# Stromversorgung-2.net
KiCad netlist of a schematic drawn in EAGLE
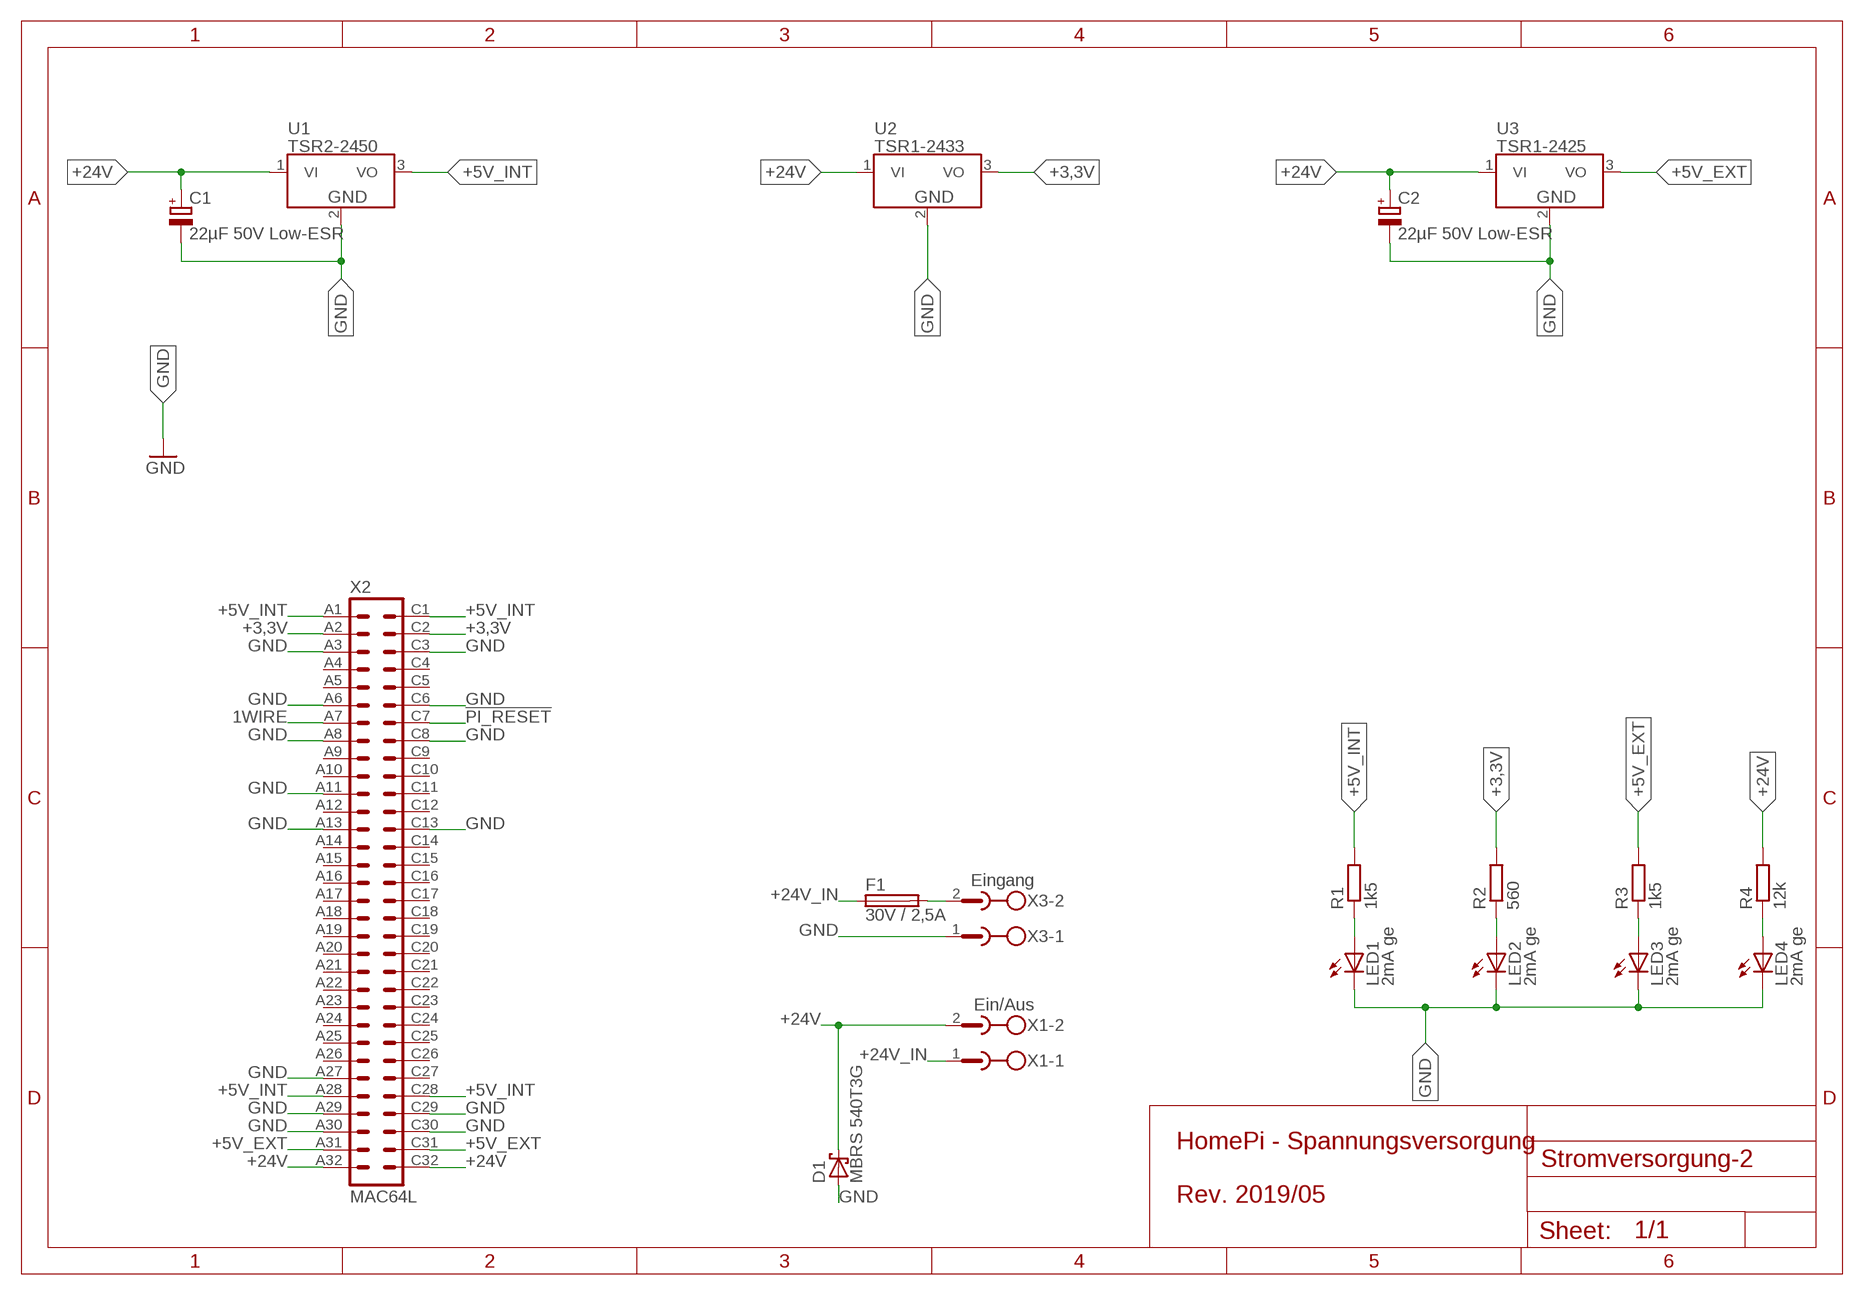
[diagram p0: schematic, sheet 1]

(export (version "E")
  (design (tool "Eeschema 10.0.6"))
  (components
    (comp (ref "C1")
      (value "22µF 50V Low-ESR")
      (footprint "eagle-import:E2-5")
      (libsource (lib "eagle-import") (part "CPOL-EUE2-5"))
    )
    (comp (ref "C2")
      (value "22µF 50V Low-ESR")
      (footprint "eagle-import:E2-5")
      (libsource (lib "eagle-import") (part "CPOL-EUE2-5"))
    )
    (comp (ref "D1")
      (value "MBRS 540T3G")
      (footprint "eagle-import:SMC")
      (libsource (lib "eagle-import") (part "SCHOTTKY-DIODESMC"))
    )
    (comp (ref "F1")
      (value "30V / 2,5A")
      (footprint "eagle-import:LITTLEFUSE")
      (libsource (lib "eagle-import") (part "LITTLEFUSE"))
    )
    (comp (ref "LED1")
      (value "2mA ge")
      (footprint "eagle-import:LED3MM")
      (libsource (lib "eagle-import") (part "LED3MM"))
    )
    (comp (ref "LED2")
      (value "2mA ge")
      (footprint "eagle-import:LED3MM")
      (libsource (lib "eagle-import") (part "LED3MM"))
    )
    (comp (ref "LED3")
      (value "2mA ge")
      (footprint "eagle-import:LED3MM")
      (libsource (lib "eagle-import") (part "LED3MM"))
    )
    (comp (ref "LED4")
      (value "2mA ge")
      (footprint "eagle-import:LED3MM")
      (libsource (lib "eagle-import") (part "LED3MM"))
    )
    (comp (ref "R1")
      (value "1k5")
      (footprint "eagle-import:R1206")
      (libsource (lib "eagle-import") (part "R-EU_R1206"))
    )
    (comp (ref "R2")
      (value "560")
      (footprint "eagle-import:R1206")
      (libsource (lib "eagle-import") (part "R-EU_R1206"))
    )
    (comp (ref "R3")
      (value "1k5")
      (footprint "eagle-import:R1206")
      (libsource (lib "eagle-import") (part "R-EU_R1206"))
    )
    (comp (ref "R4")
      (value "12k")
      (footprint "eagle-import:R1206")
      (libsource (lib "eagle-import") (part "R-EU_R1206"))
    )
    (comp (ref "U1")
      (value "TSR2-2450")
      (footprint "eagle-import:TSR2")
      (libsource (lib "eagle-import") (part "TSR2-2450"))
    )
    (comp (ref "U2")
      (value "TSR1-2433")
      (footprint "eagle-import:TSR1")
      (libsource (lib "eagle-import") (part "TSR1-2433"))
    )
    (comp (ref "U3")
      (value "TSR1-2425")
      (footprint "eagle-import:TSR1")
      (libsource (lib "eagle-import") (part "TSR1-2425"))
    )
    (comp (ref "X1")
      (value "Ein/Aus")
      (footprint "eagle-import:MSTBA2")
      (fields (field (name "MF") "FARNELL") (field (name "MPN") "1757242"))
      (libsource (lib "eagle-import") (part "MSTBA2"))
    )
    (comp (ref "X2")
      (value "MAC64L")
      (footprint "eagle-import:MAC64L")
      (libsource (lib "eagle-import") (part "MAC64L"))
    )
    (comp (ref "X3")
      (value "Eingang")
      (footprint "eagle-import:MSTBA2")
      (fields (field (name "MF") "FARNELL") (field (name "MPN") "1757242"))
      (libsource (lib "eagle-import") (part "MSTBA2"))
    )
  )
  (nets
    (net (code "1") (name "+3,3V") (class "Default")
      (node (ref "R2") (pin "2") (pinfunction "2_2") (pintype "passive"))
      (node (ref "U2") (pin "3") (pinfunction "VO_3") (pintype "power_in"))
      (node (ref "X2") (pin "A2") (pinfunction "A2_A2") (pintype "passive"))
      (node (ref "X2") (pin "C2") (pinfunction "C2_C2") (pintype "passive"))
    )
    (net (code "2") (name "+5V_EXT") (class "Default")
      (node (ref "R3") (pin "2") (pinfunction "2_2") (pintype "passive"))
      (node (ref "U3") (pin "3") (pinfunction "VO_3") (pintype "power_in"))
      (node (ref "X2") (pin "A31") (pinfunction "A31_A31") (pintype "passive"))
      (node (ref "X2") (pin "C31") (pinfunction "C31_C31") (pintype "passive"))
    )
    (net (code "3") (name "+5V_INT") (class "Default")
      (node (ref "R1") (pin "2") (pinfunction "2_2") (pintype "passive"))
      (node (ref "U1") (pin "3") (pinfunction "VO_3") (pintype "power_in"))
      (node (ref "X2") (pin "A1") (pinfunction "A1_A1") (pintype "passive"))
      (node (ref "X2") (pin "A28") (pinfunction "A28_A28") (pintype "passive"))
      (node (ref "X2") (pin "C1") (pinfunction "C1_C1") (pintype "passive"))
      (node (ref "X2") (pin "C28") (pinfunction "C28_C28") (pintype "passive"))
    )
    (net (code "4") (name "+24V") (class "Default")
      (node (ref "C1") (pin "+") (pinfunction "+_+") (pintype "passive"))
      (node (ref "C2") (pin "+") (pinfunction "+_+") (pintype "passive"))
      (node (ref "D1") (pin "C") (pinfunction "C_C") (pintype "passive"))
      (node (ref "R4") (pin "2") (pinfunction "2_2") (pintype "passive"))
      (node (ref "U1") (pin "1") (pinfunction "VI_1") (pintype "power_in"))
      (node (ref "U2") (pin "1") (pinfunction "VI_1") (pintype "power_in"))
      (node (ref "U3") (pin "1") (pinfunction "VI_1") (pintype "power_in"))
      (node (ref "X1") (pin "2") (pinfunction "1_2") (pintype "passive"))
      (node (ref "X2") (pin "A32") (pinfunction "A32_A32") (pintype "passive"))
      (node (ref "X2") (pin "C32") (pinfunction "C32_C32") (pintype "passive"))
    )
    (net (code "5") (name "/+24V_IN") (class "Default")
      (node (ref "F1") (pin "1") (pinfunction "1_1") (pintype "passive"))
      (node (ref "X1") (pin "1") (pinfunction "1_1") (pintype "passive"))
    )
    (net (code "6") (name "/1WIRE") (class "Default")
      (node (ref "X2") (pin "A7") (pinfunction "A7_A7") (pintype "passive"))
    )
    (net (code "7") (name "/~{PI_RESET}") (class "Default")
      (node (ref "X2") (pin "C7") (pinfunction "C7_C7") (pintype "passive"))
    )
    (net (code "8") (name "GND") (class "Default")
      (node (ref "C1") (pin "-") (pinfunction "-_-") (pintype "passive"))
      (node (ref "C2") (pin "-") (pinfunction "-_-") (pintype "passive"))
      (node (ref "D1") (pin "A") (pinfunction "A_A") (pintype "passive"))
      (node (ref "LED1") (pin "K") (pinfunction "C_K") (pintype "passive"))
      (node (ref "LED2") (pin "K") (pinfunction "C_K") (pintype "passive"))
      (node (ref "LED3") (pin "K") (pinfunction "C_K") (pintype "passive"))
      (node (ref "LED4") (pin "K") (pinfunction "C_K") (pintype "passive"))
      (node (ref "U1") (pin "2") (pinfunction "GND_2") (pintype "power_in"))
      (node (ref "U2") (pin "2") (pinfunction "GND_2") (pintype "power_in"))
      (node (ref "U3") (pin "2") (pinfunction "GND_2") (pintype "power_in"))
      (node (ref "X2") (pin "A11") (pinfunction "A11_A11") (pintype "passive"))
      (node (ref "X2") (pin "A13") (pinfunction "A13_A13") (pintype "passive"))
      (node (ref "X2") (pin "A27") (pinfunction "A27_A27") (pintype "passive"))
      (node (ref "X2") (pin "A29") (pinfunction "A29_A29") (pintype "passive"))
      (node (ref "X2") (pin "A3") (pinfunction "A3_A3") (pintype "passive"))
      (node (ref "X2") (pin "A30") (pinfunction "A30_A30") (pintype "passive"))
      (node (ref "X2") (pin "A6") (pinfunction "A6_A6") (pintype "passive"))
      (node (ref "X2") (pin "A8") (pinfunction "A8_A8") (pintype "passive"))
      (node (ref "X2") (pin "C13") (pinfunction "C13_C13") (pintype "passive"))
      (node (ref "X2") (pin "C29") (pinfunction "C29_C29") (pintype "passive"))
      (node (ref "X2") (pin "C3") (pinfunction "C3_C3") (pintype "passive"))
      (node (ref "X2") (pin "C30") (pinfunction "C30_C30") (pintype "passive"))
      (node (ref "X2") (pin "C6") (pinfunction "C6_C6") (pintype "passive"))
      (node (ref "X2") (pin "C8") (pinfunction "C8_C8") (pintype "passive"))
      (node (ref "X3") (pin "1") (pinfunction "1_1") (pintype "passive"))
    )
    (net (code "9") (name "Net-(LED1-PadA)") (class "Default")
      (node (ref "LED1") (pin "A") (pinfunction "A_A") (pintype "passive"))
      (node (ref "R1") (pin "1") (pinfunction "1_1") (pintype "passive"))
    )
    (net (code "10") (name "Net-(LED2-PadA)") (class "Default")
      (node (ref "LED2") (pin "A") (pinfunction "A_A") (pintype "passive"))
      (node (ref "R2") (pin "1") (pinfunction "1_1") (pintype "passive"))
    )
    (net (code "11") (name "Net-(LED3-PadA)") (class "Default")
      (node (ref "LED3") (pin "A") (pinfunction "A_A") (pintype "passive"))
      (node (ref "R3") (pin "1") (pinfunction "1_1") (pintype "passive"))
    )
    (net (code "12") (name "Net-(LED4-PadA)") (class "Default")
      (node (ref "LED4") (pin "A") (pinfunction "A_A") (pintype "passive"))
      (node (ref "R4") (pin "1") (pinfunction "1_1") (pintype "passive"))
    )
    (net (code "13") (name "Net-(X3B-1)") (class "Default")
      (node (ref "F1") (pin "2") (pinfunction "2_2") (pintype "passive"))
      (node (ref "X3") (pin "2") (pinfunction "1_2") (pintype "passive"))
    )
    (net (code "14") (name "unconnected-(X2-PadA4)") (class "Default")
      (node (ref "X2") (pin "A4") (pinfunction "A4_A4") (pintype "passive"))
    )
    (net (code "15") (name "unconnected-(X2-PadA5)") (class "Default")
      (node (ref "X2") (pin "A5") (pinfunction "A5_A5") (pintype "passive"))
    )
    (net (code "16") (name "unconnected-(X2-PadA9)") (class "Default")
      (node (ref "X2") (pin "A9") (pinfunction "A9_A9") (pintype "passive"))
    )
    (net (code "17") (name "unconnected-(X2-PadA10)") (class "Default")
      (node (ref "X2") (pin "A10") (pinfunction "A10_A10") (pintype "passive"))
    )
    (net (code "18") (name "unconnected-(X2-PadA12)") (class "Default")
      (node (ref "X2") (pin "A12") (pinfunction "A12_A12") (pintype "passive"))
    )
    (net (code "19") (name "unconnected-(X2-PadA14)") (class "Default")
      (node (ref "X2") (pin "A14") (pinfunction "A14_A14") (pintype "passive"))
    )
    (net (code "20") (name "unconnected-(X2-PadA15)") (class "Default")
      (node (ref "X2") (pin "A15") (pinfunction "A15_A15") (pintype "passive"))
    )
    (net (code "21") (name "unconnected-(X2-PadA16)") (class "Default")
      (node (ref "X2") (pin "A16") (pinfunction "A16_A16") (pintype "passive"))
    )
    (net (code "22") (name "unconnected-(X2-PadA17)") (class "Default")
      (node (ref "X2") (pin "A17") (pinfunction "A17_A17") (pintype "passive"))
    )
    (net (code "23") (name "unconnected-(X2-PadA18)") (class "Default")
      (node (ref "X2") (pin "A18") (pinfunction "A18_A18") (pintype "passive"))
    )
    (net (code "24") (name "unconnected-(X2-PadA19)") (class "Default")
      (node (ref "X2") (pin "A19") (pinfunction "A19_A19") (pintype "passive"))
    )
    (net (code "25") (name "unconnected-(X2-PadA20)") (class "Default")
      (node (ref "X2") (pin "A20") (pinfunction "A20_A20") (pintype "passive"))
    )
    (net (code "26") (name "unconnected-(X2-PadA21)") (class "Default")
      (node (ref "X2") (pin "A21") (pinfunction "A21_A21") (pintype "passive"))
    )
    (net (code "27") (name "unconnected-(X2-PadA22)") (class "Default")
      (node (ref "X2") (pin "A22") (pinfunction "A22_A22") (pintype "passive"))
    )
    (net (code "28") (name "unconnected-(X2-PadA23)") (class "Default")
      (node (ref "X2") (pin "A23") (pinfunction "A23_A23") (pintype "passive"))
    )
    (net (code "29") (name "unconnected-(X2-PadA24)") (class "Default")
      (node (ref "X2") (pin "A24") (pinfunction "A24_A24") (pintype "passive"))
    )
    (net (code "30") (name "unconnected-(X2-PadA25)") (class "Default")
      (node (ref "X2") (pin "A25") (pinfunction "A25_A25") (pintype "passive"))
    )
    (net (code "31") (name "unconnected-(X2-PadA26)") (class "Default")
      (node (ref "X2") (pin "A26") (pinfunction "A26_A26") (pintype "passive"))
    )
    (net (code "32") (name "unconnected-(X2-PadC4)") (class "Default")
      (node (ref "X2") (pin "C4") (pinfunction "C4_C4") (pintype "passive"))
    )
    (net (code "33") (name "unconnected-(X2-PadC5)") (class "Default")
      (node (ref "X2") (pin "C5") (pinfunction "C5_C5") (pintype "passive"))
    )
    (net (code "34") (name "unconnected-(X2-PadC9)") (class "Default")
      (node (ref "X2") (pin "C9") (pinfunction "C9_C9") (pintype "passive"))
    )
    (net (code "35") (name "unconnected-(X2-PadC10)") (class "Default")
      (node (ref "X2") (pin "C10") (pinfunction "C10_C10") (pintype "passive"))
    )
    (net (code "36") (name "unconnected-(X2-PadC11)") (class "Default")
      (node (ref "X2") (pin "C11") (pinfunction "C11_C11") (pintype "passive"))
    )
    (net (code "37") (name "unconnected-(X2-PadC12)") (class "Default")
      (node (ref "X2") (pin "C12") (pinfunction "C12_C12") (pintype "passive"))
    )
    (net (code "38") (name "unconnected-(X2-PadC14)") (class "Default")
      (node (ref "X2") (pin "C14") (pinfunction "C14_C14") (pintype "passive"))
    )
    (net (code "39") (name "unconnected-(X2-PadC15)") (class "Default")
      (node (ref "X2") (pin "C15") (pinfunction "C15_C15") (pintype "passive"))
    )
    (net (code "40") (name "unconnected-(X2-PadC16)") (class "Default")
      (node (ref "X2") (pin "C16") (pinfunction "C16_C16") (pintype "passive"))
    )
    (net (code "41") (name "unconnected-(X2-PadC17)") (class "Default")
      (node (ref "X2") (pin "C17") (pinfunction "C17_C17") (pintype "passive"))
    )
    (net (code "42") (name "unconnected-(X2-PadC18)") (class "Default")
      (node (ref "X2") (pin "C18") (pinfunction "C18_C18") (pintype "passive"))
    )
    (net (code "43") (name "unconnected-(X2-PadC19)") (class "Default")
      (node (ref "X2") (pin "C19") (pinfunction "C19_C19") (pintype "passive"))
    )
    (net (code "44") (name "unconnected-(X2-PadC20)") (class "Default")
      (node (ref "X2") (pin "C20") (pinfunction "C20_C20") (pintype "passive"))
    )
    (net (code "45") (name "unconnected-(X2-PadC21)") (class "Default")
      (node (ref "X2") (pin "C21") (pinfunction "C21_C21") (pintype "passive"))
    )
    (net (code "46") (name "unconnected-(X2-PadC22)") (class "Default")
      (node (ref "X2") (pin "C22") (pinfunction "C22_C22") (pintype "passive"))
    )
    (net (code "47") (name "unconnected-(X2-PadC23)") (class "Default")
      (node (ref "X2") (pin "C23") (pinfunction "C23_C23") (pintype "passive"))
    )
    (net (code "48") (name "unconnected-(X2-PadC24)") (class "Default")
      (node (ref "X2") (pin "C24") (pinfunction "C24_C24") (pintype "passive"))
    )
    (net (code "49") (name "unconnected-(X2-PadC25)") (class "Default")
      (node (ref "X2") (pin "C25") (pinfunction "C25_C25") (pintype "passive"))
    )
    (net (code "50") (name "unconnected-(X2-PadC26)") (class "Default")
      (node (ref "X2") (pin "C26") (pinfunction "C26_C26") (pintype "passive"))
    )
    (net (code "51") (name "unconnected-(X2-PadC27)") (class "Default")
      (node (ref "X2") (pin "C27") (pinfunction "C27_C27") (pintype "passive"))
    )
  )
)
